# TELM0002ADC.net
KiCad netlist of a schematic drawn in Altium Designer
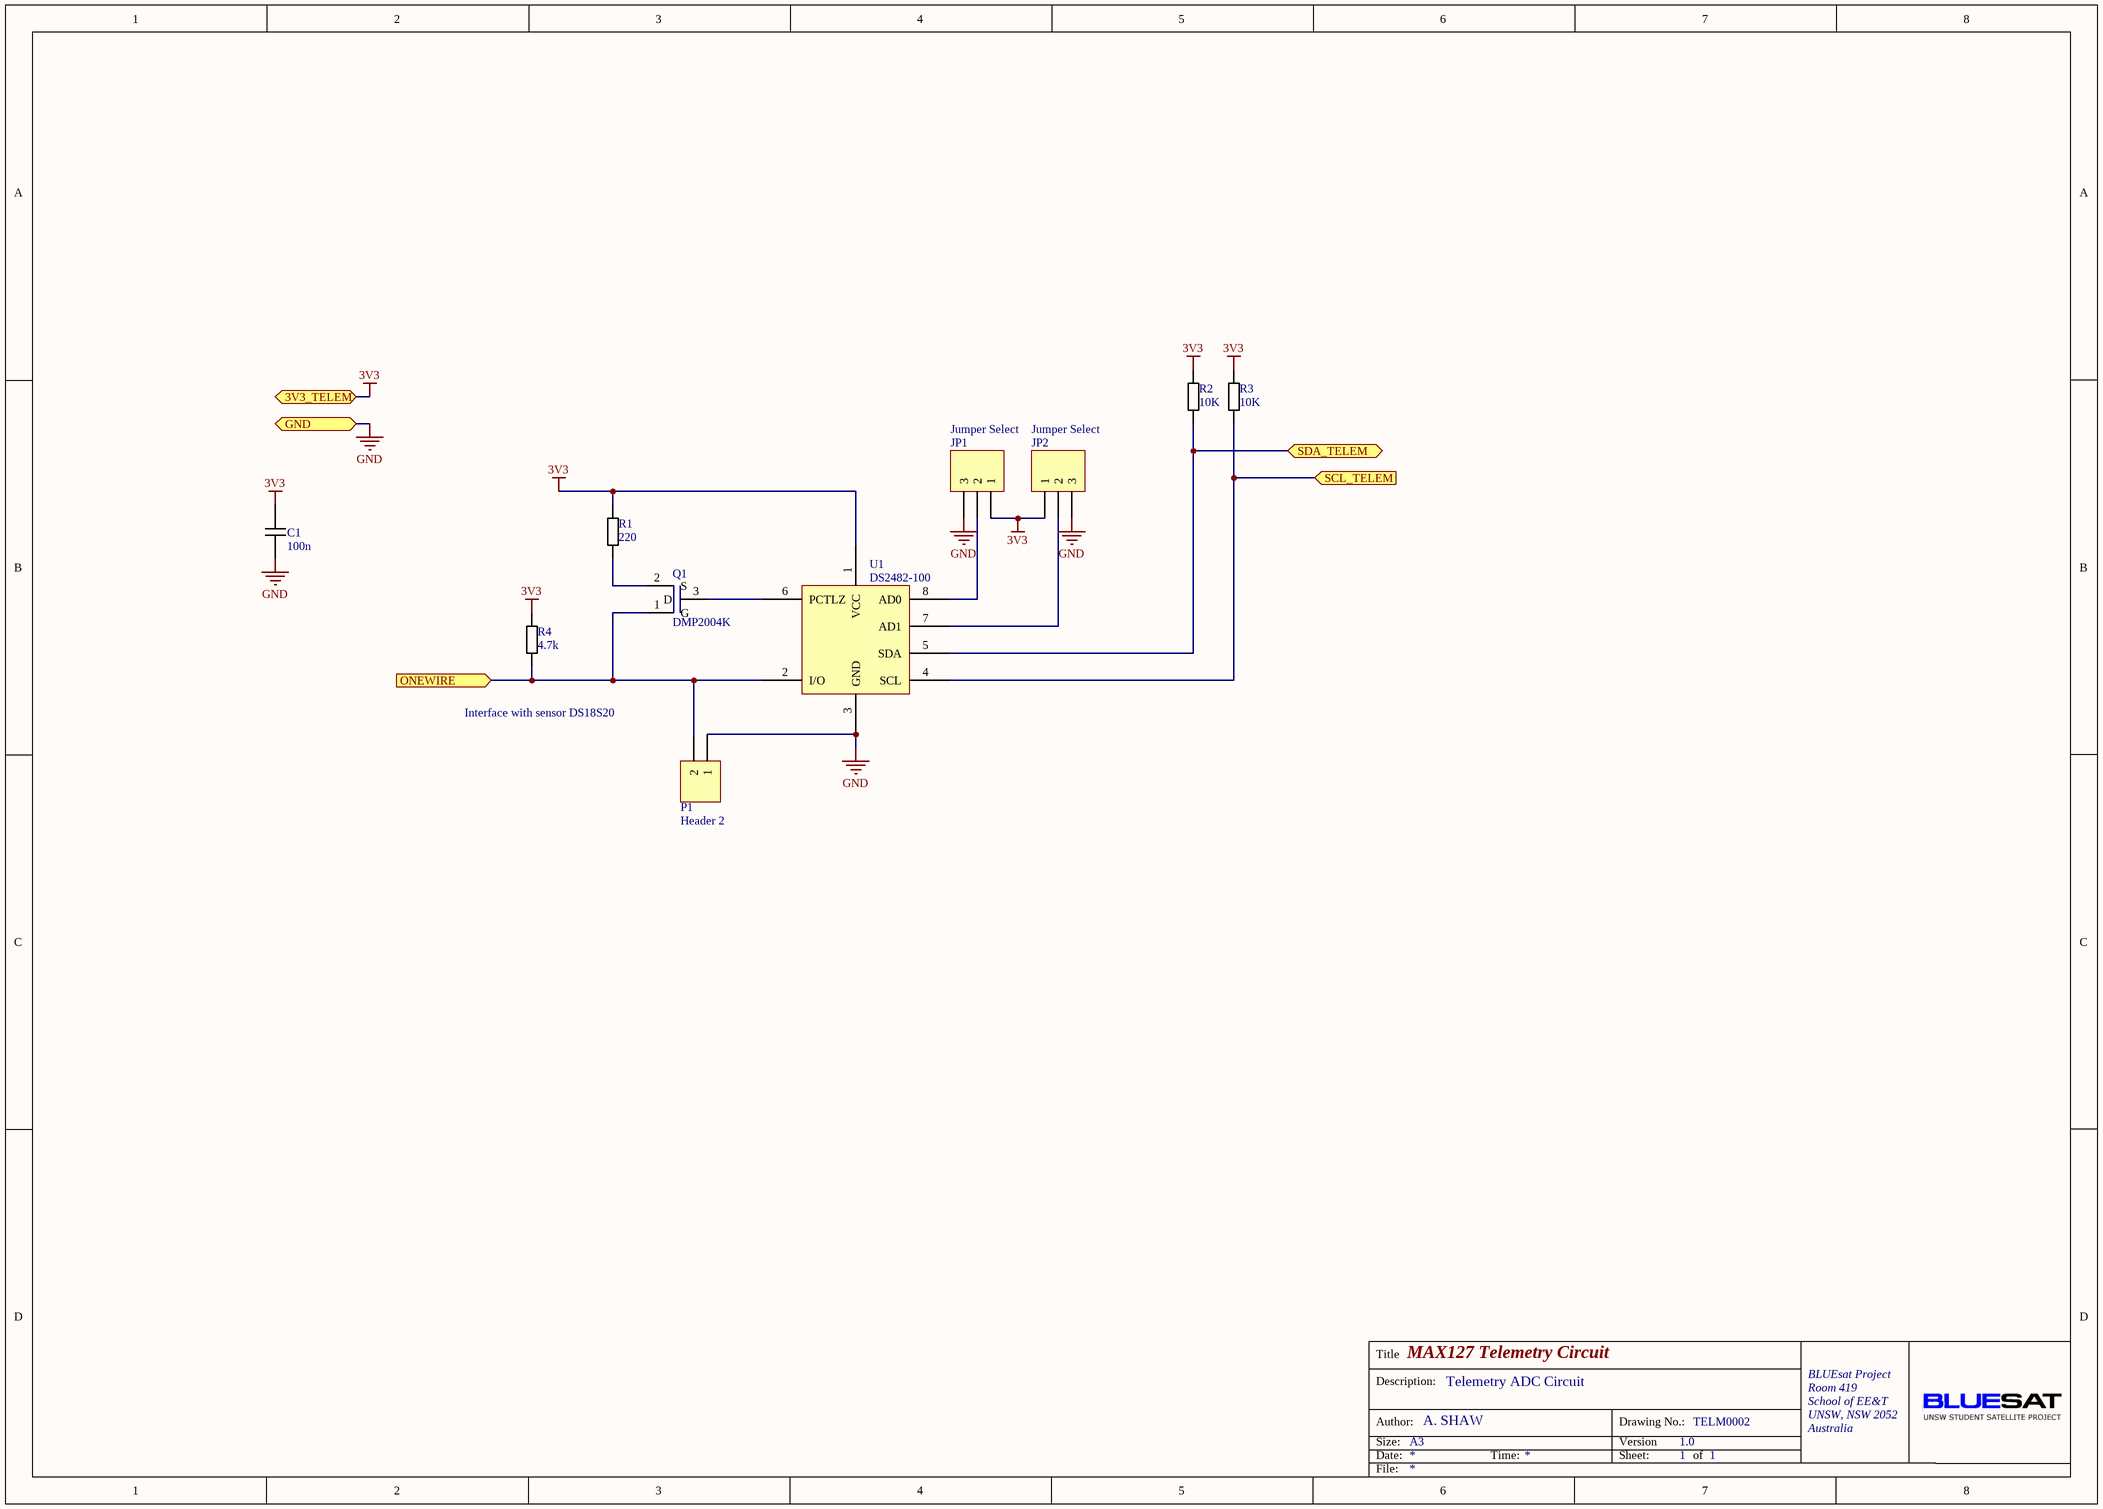
[diagram p0: TELM0002ADC.SchDoc]

(export (version "E")
  (design (tool "Eeschema 10.0.6"))
  (components
    (comp (ref "C1")
      (value "100n")
      (footprint "0805 Cap")
      (description "0805 MLCC - X7R, 10%")
      (fields (field (name "MANUFACTURER") "Kit") (field (name "Comment") "0805 Cap"))
      (libsource (lib "Tray 3 V2.0") (part "0805 MLCC - X7R, 10%"))
    )
    (comp (ref "JP1")
      (value "Jumper Select")
      (footprint "SOLDER_JUMPER_3_A")
      (description "Header, 3-Pin")
      (libsource (lib "Tray 3") (part "Header 3"))
    )
    (comp (ref "JP2")
      (value "Jumper Select")
      (footprint "SOLDER_JUMPER_3_A")
      (description "Header, 3-Pin")
      (libsource (lib "Tray 3 V2.0") (part "Header 3"))
    )
    (comp (ref "P1")
      (value "Header 2")
      (footprint "HDR1X2")
      (description "Header, 2-Pin")
      (libsource (lib "Tray 3 V2.0") (part "Header 2"))
    )
    (comp (ref "Q1")
      (value "DMP2004K")
      (footprint "DMP2004KDITR-ND")
      (description "MOSFET P-CH 20V 600MA SOT23-3")
      (fields (field (name "MANUFACTURER") "Diodes Inc."))
      (libsource (lib "Tray 3 V2.0") (part "DMP2004K"))
    )
    (comp (ref "R1")
      (value "220")
      (footprint "0805 Resistor")
      (description "0805 Thick Film Resistor 1%")
      (fields (field (name "MANUFACTURER") "Kit") (field (name "Comment") "0805 Resistor"))
      (libsource (lib "Tray 3 V2.0") (part "0805 Thick Film Resistor 1%"))
    )
    (comp (ref "R2")
      (value "10K")
      (footprint "0805 Resistor")
      (description "0805 Thick Film Resistor 1%")
      (fields (field (name "MANUFACTURER") "Kit") (field (name "Comment") "0805 Resistor"))
      (libsource (lib "Tray 3 V2.0") (part "0805 Thick Film Resistor 1%"))
    )
    (comp (ref "R3")
      (value "10K")
      (footprint "0805 Resistor")
      (description "0805 Thick Film Resistor 1%")
      (fields (field (name "MANUFACTURER") "Kit") (field (name "Comment") "0805 Resistor"))
      (libsource (lib "Tray 3 V2.0") (part "0805 Thick Film Resistor 1%"))
    )
    (comp (ref "R4")
      (value "4.7k")
      (footprint "0805 Resistor")
      (description "0805 Thick Film Resistor 1%")
      (fields (field (name "MANUFACTURER") "Kit") (field (name "Comment") "0805 Resistor"))
      (libsource (lib "Tray 3 V2.0") (part "0805 Thick Film Resistor 1%"))
    )
    (comp (ref "U1")
      (value "DS2482-100")
      (footprint "DS2482-100")
      (description "I2C to 1-Wire Master")
      (fields (field (name "MANUFACTURER") "Maxim"))
      (libsource (lib "Tray 3 V2.0") (part "DS2482-100"))
    )
  )
  (nets
    (net (code "1") (name "/ONEWIRE") (class "Default")
      (node (ref "P1") (pin "2") (pinfunction "2_2") (pintype "passive"))
      (node (ref "Q1") (pin "1") (pinfunction "G_1") (pintype "passive"))
      (node (ref "R4") (pin "1") (pinfunction "1_1") (pintype "passive"))
      (node (ref "U1") (pin "2") (pinfunction "I/O_2") (pintype "passive"))
    )
    (net (code "2") (name "/SCL_TELEM") (class "Default")
      (node (ref "R3") (pin "1") (pinfunction "1_1") (pintype "passive"))
      (node (ref "U1") (pin "4") (pinfunction "SCL_4") (pintype "passive"))
    )
    (net (code "3") (name "/SDA_TELEM") (class "Default")
      (node (ref "R2") (pin "1") (pinfunction "1_1") (pintype "passive"))
      (node (ref "U1") (pin "5") (pinfunction "SDA_5") (pintype "passive"))
    )
    (net (code "4") (name "3V3") (class "Default")
      (node (ref "C1") (pin "2") (pinfunction "2_2") (pintype "passive"))
      (node (ref "JP1") (pin "1") (pinfunction "1_1") (pintype "passive"))
      (node (ref "JP2") (pin "1") (pinfunction "1_1") (pintype "passive"))
      (node (ref "R1") (pin "2") (pinfunction "2_2") (pintype "passive"))
      (node (ref "R2") (pin "2") (pinfunction "2_2") (pintype "passive"))
      (node (ref "R3") (pin "2") (pinfunction "2_2") (pintype "passive"))
      (node (ref "R4") (pin "2") (pinfunction "2_2") (pintype "passive"))
      (node (ref "U1") (pin "1") (pinfunction "VCC_1") (pintype "passive"))
    )
    (net (code "5") (name "GND") (class "Default")
      (node (ref "C1") (pin "1") (pinfunction "1_1") (pintype "passive"))
      (node (ref "JP1") (pin "3") (pinfunction "3_3") (pintype "passive"))
      (node (ref "JP2") (pin "3") (pinfunction "3_3") (pintype "passive"))
      (node (ref "P1") (pin "1") (pinfunction "1_1") (pintype "passive"))
      (node (ref "U1") (pin "3") (pinfunction "GND_3") (pintype "passive"))
    )
    (net (code "6") (name "Net-(Q1-D)") (class "Default")
      (node (ref "Q1") (pin "3") (pinfunction "D_3") (pintype "passive"))
      (node (ref "U1") (pin "6") (pinfunction "PCTLZ_6") (pintype "passive"))
    )
    (net (code "7") (name "Net-(Q1-S)") (class "Default")
      (node (ref "Q1") (pin "2") (pinfunction "S_2") (pintype "passive"))
      (node (ref "R1") (pin "1") (pinfunction "1_1") (pintype "passive"))
    )
    (net (code "8") (name "Net-(U1-AD0)") (class "Default")
      (node (ref "JP1") (pin "2") (pinfunction "2_2") (pintype "passive"))
      (node (ref "U1") (pin "8") (pinfunction "AD0_8") (pintype "passive"))
    )
    (net (code "9") (name "Net-(U1-AD1)") (class "Default")
      (node (ref "JP2") (pin "2") (pinfunction "2_2") (pintype "passive"))
      (node (ref "U1") (pin "7") (pinfunction "AD1_7") (pintype "passive"))
    )
  )
)
